# p2c-001.net
KiCad netlist of a schematic drawn in EAGLE
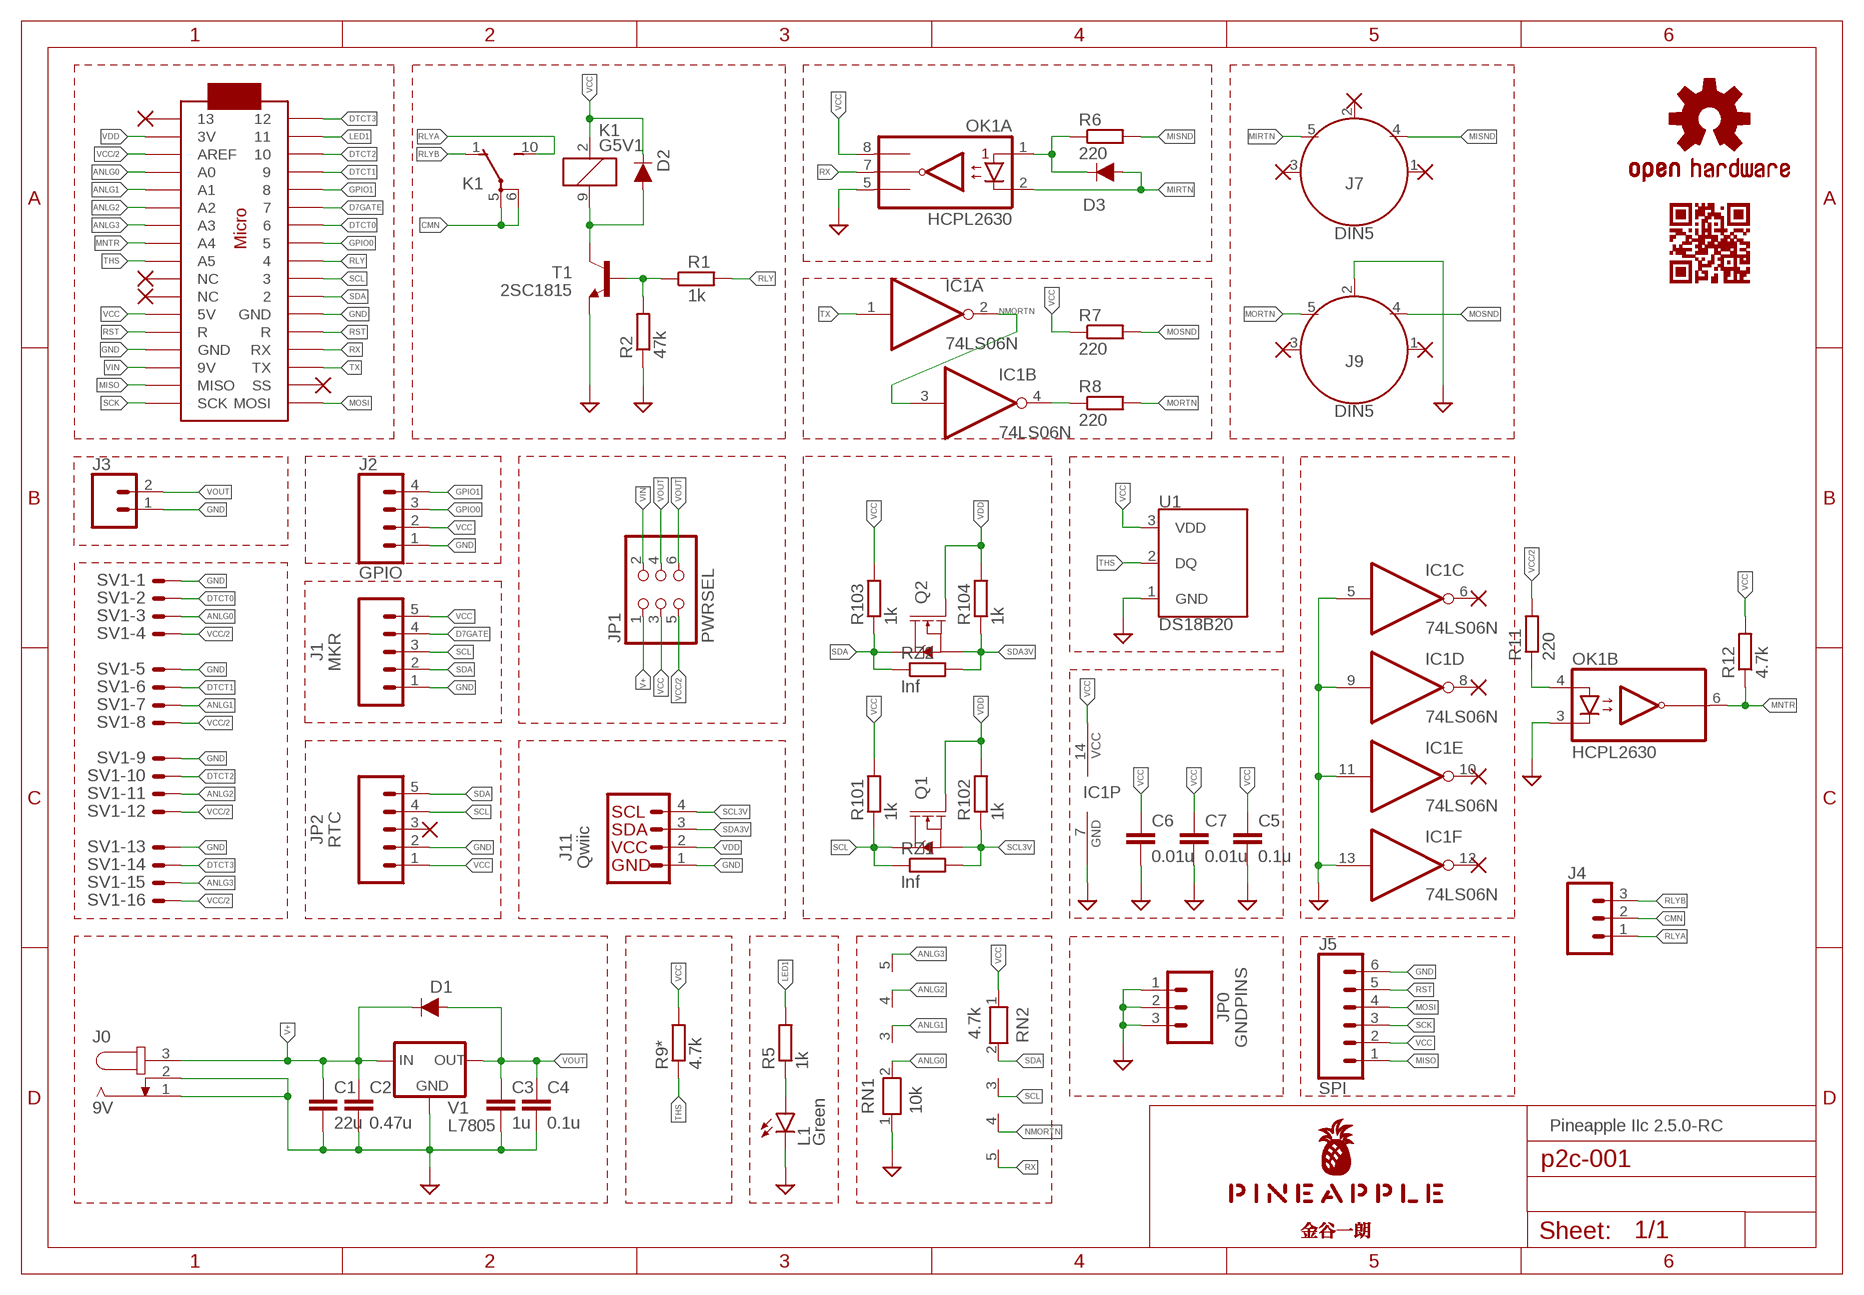
[diagram p0: schematic, sheet 1]

(export (version "E")
  (design (tool "Eeschema 10.0.6"))
  (components
    (comp (ref "C1")
      (value "22u")
      (footprint "eagle-import:C025-050X050")
      (libsource (lib "eagle-import") (part "C-EU025-050X050"))
    )
    (comp (ref "C2")
      (value "0.47u")
      (footprint "eagle-import:C050-024X044")
      (libsource (lib "eagle-import") (part "C-EU050-024X044"))
    )
    (comp (ref "C3")
      (value "1u")
      (footprint "eagle-import:C050-024X044")
      (libsource (lib "eagle-import") (part "C-EU050-024X044"))
    )
    (comp (ref "C4")
      (value "0.1u")
      (footprint "eagle-import:C025-024X044")
      (libsource (lib "eagle-import") (part "C-EU025-024X044"))
    )
    (comp (ref "C5")
      (value "0.1u")
      (footprint "eagle-import:C025-024X044")
      (libsource (lib "eagle-import") (part "C-EU025-024X044"))
    )
    (comp (ref "C6")
      (value "0.01u")
      (footprint "eagle-import:C025-024X044")
      (libsource (lib "eagle-import") (part "resistor_348_C-EU025-024X044"))
    )
    (comp (ref "C7")
      (value "0.01u")
      (footprint "eagle-import:C025-024X044")
      (libsource (lib "eagle-import") (part "resistor_348_C-EU025-024X044"))
    )
    (comp (ref "D1")
      (value "DIODE-1N4148")
      (footprint "eagle-import:DIODE-1N4148")
      (libsource (lib "eagle-import") (part "DIODE-1N4148"))
    )
    (comp (ref "D2")
      (value "DIODE-1N4148")
      (footprint "eagle-import:DIODE-1N4148")
      (libsource (lib "eagle-import") (part "DIODE-1N4148"))
    )
    (comp (ref "D3")
      (value "DIODE-1N4148")
      (footprint "eagle-import:DIODE-1N4148")
      (libsource (lib "eagle-import") (part "DIODE-1N4148"))
    )
    (comp (ref "IC1")
      (value "74LS06N")
      (footprint "eagle-import:DIL14")
      (libsource (lib "eagle-import") (part "7406NLS"))
    )
    (comp (ref "J0")
      (value "9V")
      (footprint "eagle-import:SPC4077")
      (libsource (lib "eagle-import") (part "JACK-PLUG0"))
    )
    (comp (ref "J1")
      (value "MKR")
      (footprint "eagle-import:JST-5-PTH")
      (libsource (lib "eagle-import") (part "CONN_05JST"))
    )
    (comp (ref "J2")
      (value "GPIO")
      (footprint "eagle-import:JST-4-PTH")
      (libsource (lib "eagle-import") (part "CONN_04JST-PTH"))
    )
    (comp (ref "J3")
      (value "CONN_02JST-PTH-2")
      (footprint "eagle-import:JST-2-PTH")
      (libsource (lib "eagle-import") (part "CONN_02JST-PTH-2"))
    )
    (comp (ref "J4")
      (value "CONN_03JST-PTH-NS")
      (footprint "eagle-import:JST-3-PTH-NS")
      (libsource (lib "eagle-import") (part "CONN_03JST-PTH-NS"))
    )
    (comp (ref "J5")
      (value "SPI")
      (footprint "eagle-import:1X06_1.27MM")
      (libsource (lib "eagle-import") (part "CONN_061.27MM"))
    )
    (comp (ref "J7")
      (value "DIN5")
      (footprint "eagle-import:DIN5-RA-PTH")
      (libsource (lib "eagle-import") (part "DIN5"))
    )
    (comp (ref "J9")
      (value "DIN5")
      (footprint "eagle-import:DIN5-RA-PTH")
      (libsource (lib "eagle-import") (part "DIN5"))
    )
    (comp (ref "J11")
      (value "Qwiic")
      (footprint "eagle-import:1X04_1MM_RA")
      (libsource (lib "eagle-import") (part "QWIIC_CONNECTORJS-1MM"))
    )
    (comp (ref "JP0")
      (value "GNDPINS")
      (footprint "eagle-import:1X03")
      (libsource (lib "eagle-import") (part "CONN_03"))
    )
    (comp (ref "JP1")
      (value "PWRSEL")
      (footprint "eagle-import:2X03")
      (libsource (lib "eagle-import") (part "PINHD-2X3"))
    )
    (comp (ref "JP2")
      (value "RTC")
      (footprint "eagle-import:1X05")
      (libsource (lib "eagle-import") (part "CONN_05"))
    )
    (comp (ref "K1")
      (value "G5V1")
      (footprint "eagle-import:G5V1")
      (fields (field (name "MPN") "G5V-1-DC24"))
      (libsource (lib "eagle-import") (part "G5V1"))
    )
    (comp (ref "L1")
      (value "Green")
      (footprint "eagle-import:LED3MM")
      (libsource (lib "eagle-import") (part "LED3MM"))
    )
    (comp (ref "LOGO1")
      (value "OSHW-LOGOS-COPPER")
      (footprint "eagle-import:OSHW-LOGO-S_COPPER")
      (libsource (lib "eagle-import") (part "OSHW-LOGOS-COPPER"))
    )
    (comp (ref "OK1")
      (value "HCPL2630")
      (footprint "eagle-import:DIL08")
      (fields (field (name "MF") "AGILENT TECHNOLOGIES") (field (name "MPN") "HCPL-2630-000E"))
      (libsource (lib "eagle-import") (part "HCPL2630"))
    )
    (comp (ref "Q1")
      (value "220mA/50V/3.5Ω")
      (footprint "eagle-import:SOT23-3")
      (libsource (lib "eagle-import") (part "MOSFET-NCH-BSS138"))
    )
    (comp (ref "Q2")
      (value "220mA/50V/3.5Ω")
      (footprint "eagle-import:SOT23-3")
      (libsource (lib "eagle-import") (part "MOSFET-NCH-BSS138"))
    )
    (comp (ref "R1")
      (value "1k")
      (footprint "eagle-import:0204_5")
      (libsource (lib "eagle-import") (part "R-EU_0204/5"))
    )
    (comp (ref "R2")
      (value "47k")
      (footprint "eagle-import:0204_5")
      (libsource (lib "eagle-import") (part "R-EU_0204/5"))
    )
    (comp (ref "R5")
      (value "1k")
      (footprint "eagle-import:0204_5")
      (libsource (lib "eagle-import") (part "R-EU_0204/5"))
    )
    (comp (ref "R6")
      (value "220")
      (footprint "eagle-import:0204_5")
      (libsource (lib "eagle-import") (part "R-EU_0204/5"))
    )
    (comp (ref "R7")
      (value "220")
      (footprint "eagle-import:0204_5")
      (libsource (lib "eagle-import") (part "R-EU_0204/5"))
    )
    (comp (ref "R8")
      (value "220")
      (footprint "eagle-import:0204_5")
      (libsource (lib "eagle-import") (part "R-EU_0204/5"))
    )
    (comp (ref "R9*")
      (value "4.7k")
      (footprint "eagle-import:0204_5")
      (libsource (lib "eagle-import") (part "R-EU_0204/5"))
    )
    (comp (ref "R11")
      (value "220")
      (footprint "eagle-import:0204_5")
      (libsource (lib "eagle-import") (part "R-EU_0204/5"))
    )
    (comp (ref "R12")
      (value "4.7k")
      (footprint "eagle-import:0204_5")
      (libsource (lib "eagle-import") (part "R-EU_0204/5"))
    )
    (comp (ref "R101")
      (value "1k")
      (footprint "eagle-import:R2012")
      (libsource (lib "eagle-import") (part "R-EU_R2012"))
    )
    (comp (ref "R102")
      (value "1k")
      (footprint "eagle-import:R2012")
      (libsource (lib "eagle-import") (part "R-EU_R2012"))
    )
    (comp (ref "R103")
      (value "1k")
      (footprint "eagle-import:R2012")
      (libsource (lib "eagle-import") (part "R-EU_R2012"))
    )
    (comp (ref "R104")
      (value "1k")
      (footprint "eagle-import:R2012")
      (libsource (lib "eagle-import") (part "R-EU_R2012"))
    )
    (comp (ref "RN1")
      (value "10k")
      (footprint "eagle-import:RN-5")
      (libsource (lib "eagle-import") (part "RN04"))
    )
    (comp (ref "RN2")
      (value "4.7k")
      (footprint "eagle-import:RN-5")
      (libsource (lib "eagle-import") (part "RN04"))
    )
    (comp (ref "RZ1")
      (value "Inf")
      (footprint "eagle-import:R2012")
      (libsource (lib "eagle-import") (part "R-EU_R2012"))
    )
    (comp (ref "RZ2")
      (value "Inf")
      (footprint "eagle-import:R2012")
      (libsource (lib "eagle-import") (part "R-EU_R2012"))
    )
    (comp (ref "SV1")
      (value "ML16LE")
      (footprint "eagle-import:ML16L")
      (libsource (lib "eagle-import") (part "ML16LE"))
    )
    (comp (ref "T1")
      (value "2SC1815")
      (footprint "eagle-import:TO92-ECB")
      (libsource (lib "eagle-import") (part "2SC1815"))
    )
    (comp (ref "U$1")
      (value "PINEAPPLE450_SILK")
      (footprint "eagle-import:PINEAPPLE450_SILK")
      (libsource (lib "eagle-import") (part "PINEAPPLE450_SILK"))
    )
    (comp (ref "U$2")
      (value "ARDUINOMICRO")
      (footprint "eagle-import:ARDUINOMICRO")
      (libsource (lib "eagle-import") (part "ARDUINOMICRO"))
    )
    (comp (ref "U$3")
      (value "KANAYA768_SILK")
      (footprint "eagle-import:KANAYA768_SILK")
      (libsource (lib "eagle-import") (part "KANAYA768_SILK"))
    )
    (comp (ref "U$4")
      (value "CARDQRCODE450_SILK")
      (footprint "eagle-import:CARDQRCODE450_SILK")
      (libsource (lib "eagle-import") (part "CARDQRCODE450_SILK"))
    )
    (comp (ref "U1")
      (value "DS18B20")
      (footprint "eagle-import:TO-92-AMMO")
      (libsource (lib "eagle-import") (part "DS18B20"))
    )
    (comp (ref "V1")
      (value "L7805")
      (footprint "eagle-import:78XXS")
      (libsource (lib "eagle-import") (part "78XXS"))
    )
  )
  (nets
    (net (code "1") (name "ANLG0") (class "Default")
      (node (ref "RN1") (pin "2") (pinfunction "2_2") (pintype "passive"))
      (node (ref "SV1") (pin "3") (pinfunction "S_3") (pintype "passive"))
      (node (ref "U$2") (pin "P$31") (pinfunction "A0_P$31") (pintype "bidirectional"))
    )
    (net (code "2") (name "ANLG1") (class "Default")
      (node (ref "RN1") (pin "3") (pinfunction "3_3") (pintype "passive"))
      (node (ref "SV1") (pin "7") (pinfunction "S_7") (pintype "passive"))
      (node (ref "U$2") (pin "P$30") (pinfunction "A1_P$30") (pintype "bidirectional"))
    )
    (net (code "3") (name "ANLG2") (class "Default")
      (node (ref "RN1") (pin "4") (pinfunction "4_4") (pintype "passive"))
      (node (ref "SV1") (pin "11") (pinfunction "S_11") (pintype "passive"))
      (node (ref "U$2") (pin "P$29") (pinfunction "A2_P$29") (pintype "bidirectional"))
    )
    (net (code "4") (name "ANLG3") (class "Default")
      (node (ref "RN1") (pin "5") (pinfunction "5_5") (pintype "passive"))
      (node (ref "SV1") (pin "15") (pinfunction "S_15") (pintype "passive"))
      (node (ref "U$2") (pin "P$28") (pinfunction "A3_P$28") (pintype "bidirectional"))
    )
    (net (code "5") (name "CMN") (class "Default")
      (node (ref "J4") (pin "2") (pinfunction "2_2") (pintype "passive"))
      (node (ref "K1") (pin "5") (pinfunction "P_5") (pintype "passive"))
      (node (ref "K1") (pin "6") (pinfunction "P_6") (pintype "passive"))
    )
    (net (code "6") (name "D7GATE") (class "Default")
      (node (ref "J1") (pin "4") (pinfunction "4_4") (pintype "passive"))
      (node (ref "U$2") (pin "P$6") (pinfunction "7_P$6") (pintype "bidirectional"))
    )
    (net (code "7") (name "DTCT0") (class "Default")
      (node (ref "SV1") (pin "2") (pinfunction "S_2") (pintype "passive"))
      (node (ref "U$2") (pin "P$7") (pinfunction "6_P$7") (pintype "bidirectional"))
    )
    (net (code "8") (name "DTCT1") (class "Default")
      (node (ref "SV1") (pin "6") (pinfunction "S_6") (pintype "passive"))
      (node (ref "U$2") (pin "P$4") (pinfunction "9_P$4") (pintype "bidirectional"))
    )
    (net (code "9") (name "DTCT2") (class "Default")
      (node (ref "SV1") (pin "10") (pinfunction "S_10") (pintype "passive"))
      (node (ref "U$2") (pin "P$3") (pinfunction "10_P$3") (pintype "bidirectional"))
    )
    (net (code "10") (name "DTCT3") (class "Default")
      (node (ref "SV1") (pin "14") (pinfunction "S_14") (pintype "passive"))
      (node (ref "U$2") (pin "P$1") (pinfunction "12_P$1") (pintype "bidirectional"))
    )
    (net (code "11") (name "GND") (class "Default")
      (node (ref "C1") (pin "2") (pinfunction "2_2") (pintype "passive"))
      (node (ref "C2") (pin "2") (pinfunction "2_2") (pintype "passive"))
      (node (ref "C3") (pin "2") (pinfunction "2_2") (pintype "passive"))
      (node (ref "C4") (pin "2") (pinfunction "2_2") (pintype "passive"))
      (node (ref "C5") (pin "2") (pinfunction "2_2") (pintype "passive"))
      (node (ref "C6") (pin "2") (pinfunction "2_2") (pintype "passive"))
      (node (ref "C7") (pin "2") (pinfunction "2_2") (pintype "passive"))
      (node (ref "IC1") (pin "11") (pinfunction "I_11") (pintype "input"))
      (node (ref "IC1") (pin "13") (pinfunction "I_13") (pintype "input"))
      (node (ref "IC1") (pin "5") (pinfunction "I_5") (pintype "input"))
      (node (ref "IC1") (pin "7") (pinfunction "GND_7") (pintype "power_in"))
      (node (ref "IC1") (pin "9") (pinfunction "I_9") (pintype "input"))
      (node (ref "J0") (pin "1") (pinfunction "1_1") (pintype "passive"))
      (node (ref "J0") (pin "2") (pinfunction "2_2") (pintype "passive"))
      (node (ref "J1") (pin "1") (pinfunction "1_1") (pintype "passive"))
      (node (ref "J11") (pin "1") (pinfunction "GND_1") (pintype "power_in"))
      (node (ref "J2") (pin "1") (pinfunction "1_1") (pintype "passive"))
      (node (ref "J3") (pin "1") (pinfunction "1_1") (pintype "passive"))
      (node (ref "J5") (pin "6") (pinfunction "6_6") (pintype "passive"))
      (node (ref "J9") (pin "2") (pinfunction "2_2") (pintype "bidirectional"))
      (node (ref "JP0") (pin "1") (pinfunction "1_1") (pintype "passive"))
      (node (ref "JP0") (pin "2") (pinfunction "2_2") (pintype "passive"))
      (node (ref "JP0") (pin "3") (pinfunction "3_3") (pintype "passive"))
      (node (ref "JP2") (pin "2") (pinfunction "2_2") (pintype "passive"))
      (node (ref "L1") (pin "K") (pinfunction "C_K") (pintype "passive"))
      (node (ref "OK1") (pin "3") (pinfunction "C2_3") (pintype "passive"))
      (node (ref "OK1") (pin "5") (pinfunction "GND_5") (pintype "passive"))
      (node (ref "R2") (pin "1") (pinfunction "1_1") (pintype "passive"))
      (node (ref "RN1") (pin "1") (pinfunction "1_1") (pintype "passive"))
      (node (ref "SV1") (pin "1") (pinfunction "S_1") (pintype "passive"))
      (node (ref "SV1") (pin "13") (pinfunction "S_13") (pintype "passive"))
      (node (ref "SV1") (pin "5") (pinfunction "S_5") (pintype "passive"))
      (node (ref "SV1") (pin "9") (pinfunction "S_9") (pintype "passive"))
      (node (ref "T1") (pin "E") (pinfunction "E_E") (pintype "passive"))
      (node (ref "U$2") (pin "P$12") (pinfunction "GND_P$12") (pintype "bidirectional"))
      (node (ref "U$2") (pin "P$21") (pinfunction "GND_P$21") (pintype "bidirectional"))
      (node (ref "U1") (pin "1") (pinfunction "GND_1") (pintype "power_in"))
      (node (ref "V1") (pin "GND") (pinfunction "GND_GND") (pintype "input"))
    )
    (net (code "12") (name "GPIO0") (class "Default")
      (node (ref "J2") (pin "3") (pinfunction "3_3") (pintype "passive"))
      (node (ref "U$2") (pin "P$8") (pinfunction "5_P$8") (pintype "bidirectional"))
    )
    (net (code "13") (name "GPIO1") (class "Default")
      (node (ref "J2") (pin "4") (pinfunction "4_4") (pintype "passive"))
      (node (ref "U$2") (pin "P$5") (pinfunction "8_P$5") (pintype "bidirectional"))
    )
    (net (code "14") (name "LED1") (class "Default")
      (node (ref "R5") (pin "2") (pinfunction "2_2") (pintype "passive"))
      (node (ref "U$2") (pin "P$2") (pinfunction "11_P$2") (pintype "bidirectional"))
    )
    (net (code "15") (name "MIRTN") (class "Default")
      (node (ref "D3") (pin "A") (pinfunction "A_A") (pintype "passive"))
      (node (ref "J7") (pin "5") (pinfunction "5_5") (pintype "bidirectional"))
      (node (ref "OK1") (pin "2") (pinfunction "C1_2") (pintype "passive"))
    )
    (net (code "16") (name "MISND") (class "Default")
      (node (ref "J7") (pin "4") (pinfunction "4_4") (pintype "bidirectional"))
      (node (ref "R6") (pin "2") (pinfunction "2_2") (pintype "passive"))
    )
    (net (code "17") (name "MISO") (class "Default")
      (node (ref "J5") (pin "1") (pinfunction "1_1") (pintype "passive"))
      (node (ref "U$2") (pin "P$19") (pinfunction "MISO_P$19") (pintype "bidirectional"))
    )
    (net (code "18") (name "MNTR") (class "Default")
      (node (ref "OK1") (pin "6") (pinfunction "VO2_6") (pintype "passive"))
      (node (ref "R12") (pin "1") (pinfunction "1_1") (pintype "passive"))
      (node (ref "U$2") (pin "P$27") (pinfunction "A4_P$27") (pintype "bidirectional"))
    )
    (net (code "19") (name "MORTN") (class "Default")
      (node (ref "J9") (pin "5") (pinfunction "5_5") (pintype "bidirectional"))
      (node (ref "R8") (pin "2") (pinfunction "2_2") (pintype "passive"))
    )
    (net (code "20") (name "MOSI") (class "Default")
      (node (ref "J5") (pin "4") (pinfunction "4_4") (pintype "passive"))
      (node (ref "U$2") (pin "P$17") (pinfunction "MOSI_P$17") (pintype "bidirectional"))
    )
    (net (code "21") (name "MOSND") (class "Default")
      (node (ref "J9") (pin "4") (pinfunction "4_4") (pintype "bidirectional"))
      (node (ref "R7") (pin "2") (pinfunction "2_2") (pintype "passive"))
    )
    (net (code "22") (name "NMORTN") (class "Default")
      (node (ref "IC1") (pin "2") (pinfunction "O_2") (pintype "open_collector"))
      (node (ref "IC1") (pin "3") (pinfunction "I_3") (pintype "input"))
      (node (ref "RN2") (pin "4") (pinfunction "4_4") (pintype "passive"))
    )
    (net (code "23") (name "Net-(IC1B-O)") (class "Default")
      (node (ref "IC1") (pin "4") (pinfunction "O_4") (pintype "open_collector"))
      (node (ref "R8") (pin "1") (pinfunction "1_1") (pintype "passive"))
    )
    (net (code "24") (name "Net-(K1A-2)") (class "Default")
      (node (ref "D2") (pin "A") (pinfunction "A_A") (pintype "passive"))
      (node (ref "K1") (pin "9") (pinfunction "2_9") (pintype "passive"))
      (node (ref "T1") (pin "C") (pinfunction "C_C") (pintype "passive"))
    )
    (net (code "25") (name "Net-(L1-PadA)") (class "Default")
      (node (ref "L1") (pin "A") (pinfunction "A_A") (pintype "passive"))
      (node (ref "R5") (pin "1") (pinfunction "1_1") (pintype "passive"))
    )
    (net (code "26") (name "Net-(OK1A-A1)") (class "Default")
      (node (ref "D3") (pin "C") (pinfunction "C_C") (pintype "passive"))
      (node (ref "OK1") (pin "1") (pinfunction "A1_1") (pintype "passive"))
      (node (ref "R6") (pin "1") (pinfunction "1_1") (pintype "passive"))
    )
    (net (code "27") (name "Net-(OK1B-A2)") (class "Default")
      (node (ref "OK1") (pin "4") (pinfunction "A2_4") (pintype "passive"))
      (node (ref "R11") (pin "1") (pinfunction "1_1") (pintype "passive"))
    )
    (net (code "28") (name "Net-(R1-Pad1)") (class "Default")
      (node (ref "R1") (pin "1") (pinfunction "1_1") (pintype "passive"))
      (node (ref "R2") (pin "2") (pinfunction "2_2") (pintype "passive"))
      (node (ref "T1") (pin "B") (pinfunction "B_B") (pintype "passive"))
    )
    (net (code "29") (name "RLY") (class "Default")
      (node (ref "R1") (pin "2") (pinfunction "2_2") (pintype "passive"))
      (node (ref "U$2") (pin "P$9") (pinfunction "4_P$9") (pintype "bidirectional"))
    )
    (net (code "30") (name "RLYA") (class "Default")
      (node (ref "J4") (pin "1") (pinfunction "1_1") (pintype "passive"))
      (node (ref "K1") (pin "10") (pinfunction "S_10") (pintype "passive"))
    )
    (net (code "31") (name "RLYB") (class "Default")
      (node (ref "J4") (pin "3") (pinfunction "3_3") (pintype "passive"))
      (node (ref "K1") (pin "1") (pinfunction "O_1") (pintype "passive"))
    )
    (net (code "32") (name "RST") (class "Default")
      (node (ref "J5") (pin "5") (pinfunction "5_5") (pintype "passive"))
      (node (ref "U$2") (pin "P$13") (pinfunction "R_P$13") (pintype "bidirectional"))
      (node (ref "U$2") (pin "P$22") (pinfunction "R_P$22") (pintype "bidirectional"))
    )
    (net (code "33") (name "RX") (class "Default")
      (node (ref "OK1") (pin "7") (pinfunction "VO1_7") (pintype "passive"))
      (node (ref "RN2") (pin "5") (pinfunction "5_5") (pintype "passive"))
      (node (ref "U$2") (pin "P$14") (pinfunction "RX_P$14") (pintype "bidirectional"))
    )
    (net (code "34") (name "SCK") (class "Default")
      (node (ref "J5") (pin "3") (pinfunction "3_3") (pintype "passive"))
      (node (ref "U$2") (pin "P$18") (pinfunction "SCK_P$18") (pintype "bidirectional"))
    )
    (net (code "35") (name "SCL") (class "Default")
      (node (ref "J1") (pin "3") (pinfunction "3_3") (pintype "passive"))
      (node (ref "JP2") (pin "4") (pinfunction "4_4") (pintype "passive"))
      (node (ref "Q1") (pin "3") (pinfunction "D_3") (pintype "bidirectional"))
      (node (ref "R101") (pin "1") (pinfunction "1_1") (pintype "passive"))
      (node (ref "RN2") (pin "3") (pinfunction "3_3") (pintype "passive"))
      (node (ref "RZ1") (pin "1") (pinfunction "1_1") (pintype "passive"))
      (node (ref "U$2") (pin "P$10") (pinfunction "3_P$10") (pintype "bidirectional"))
    )
    (net (code "36") (name "SCL3V") (class "Default")
      (node (ref "J11") (pin "4") (pinfunction "SCL_4") (pintype "passive"))
      (node (ref "Q1") (pin "2") (pinfunction "S_2") (pintype "bidirectional"))
      (node (ref "R102") (pin "1") (pinfunction "1_1") (pintype "passive"))
      (node (ref "RZ1") (pin "2") (pinfunction "2_2") (pintype "passive"))
    )
    (net (code "37") (name "SDA") (class "Default")
      (node (ref "J1") (pin "2") (pinfunction "2_2") (pintype "passive"))
      (node (ref "JP2") (pin "5") (pinfunction "5_5") (pintype "passive"))
      (node (ref "Q2") (pin "3") (pinfunction "D_3") (pintype "bidirectional"))
      (node (ref "R103") (pin "1") (pinfunction "1_1") (pintype "passive"))
      (node (ref "RN2") (pin "2") (pinfunction "2_2") (pintype "passive"))
      (node (ref "RZ2") (pin "1") (pinfunction "1_1") (pintype "passive"))
      (node (ref "U$2") (pin "P$11") (pinfunction "2_P$11") (pintype "bidirectional"))
    )
    (net (code "38") (name "SDA3V") (class "Default")
      (node (ref "J11") (pin "3") (pinfunction "SDA_3") (pintype "passive"))
      (node (ref "Q2") (pin "2") (pinfunction "S_2") (pintype "bidirectional"))
      (node (ref "R104") (pin "1") (pinfunction "1_1") (pintype "passive"))
      (node (ref "RZ2") (pin "2") (pinfunction "2_2") (pintype "passive"))
    )
    (net (code "39") (name "THS") (class "Default")
      (node (ref "R9*") (pin "1") (pinfunction "1_1") (pintype "passive"))
      (node (ref "U$2") (pin "P$26") (pinfunction "A5_P$26") (pintype "bidirectional"))
      (node (ref "U1") (pin "2") (pinfunction "DQ_2") (pintype "bidirectional"))
    )
    (net (code "40") (name "TX") (class "Default")
      (node (ref "IC1") (pin "1") (pinfunction "I_1") (pintype "input"))
      (node (ref "U$2") (pin "P$15") (pinfunction "TX_P$15") (pintype "bidirectional"))
    )
    (net (code "41") (name "V+") (class "Default")
      (node (ref "C1") (pin "1") (pinfunction "1_1") (pintype "passive"))
      (node (ref "C2") (pin "1") (pinfunction "1_1") (pintype "passive"))
      (node (ref "D1") (pin "C") (pinfunction "C_C") (pintype "passive"))
      (node (ref "J0") (pin "3") (pinfunction "3_3") (pintype "passive"))
      (node (ref "JP1") (pin "1") (pinfunction "1_1") (pintype "passive"))
      (node (ref "V1") (pin "IN") (pinfunction "IN_IN") (pintype "input"))
    )
    (net (code "42") (name "VCC") (class "Default")
      (node (ref "C5") (pin "1") (pinfunction "1_1") (pintype "passive"))
      (node (ref "C6") (pin "1") (pinfunction "1_1") (pintype "passive"))
      (node (ref "C7") (pin "1") (pinfunction "1_1") (pintype "passive"))
      (node (ref "D2") (pin "C") (pinfunction "C_C") (pintype "passive"))
      (node (ref "IC1") (pin "14") (pinfunction "VCC_14") (pintype "power_in"))
      (node (ref "J1") (pin "5") (pinfunction "5_5") (pintype "passive"))
      (node (ref "J2") (pin "2") (pinfunction "2_2") (pintype "passive"))
      (node (ref "J5") (pin "2") (pinfunction "2_2") (pintype "passive"))
      (node (ref "JP1") (pin "3") (pinfunction "3_3") (pintype "passive"))
      (node (ref "JP2") (pin "1") (pinfunction "1_1") (pintype "passive"))
      (node (ref "K1") (pin "2") (pinfunction "1_2") (pintype "passive"))
      (node (ref "OK1") (pin "8") (pinfunction "VCC_8") (pintype "passive"))
      (node (ref "R101") (pin "2") (pinfunction "2_2") (pintype "passive"))
      (node (ref "R103") (pin "2") (pinfunction "2_2") (pintype "passive"))
      (node (ref "R12") (pin "2") (pinfunction "2_2") (pintype "passive"))
      (node (ref "R7") (pin "1") (pinfunction "1_1") (pintype "passive"))
      (node (ref "R9*") (pin "2") (pinfunction "2_2") (pintype "passive"))
      (node (ref "RN2") (pin "1") (pinfunction "1_1") (pintype "passive"))
      (node (ref "U$2") (pin "P$23") (pinfunction "5V_P$23") (pintype "bidirectional"))
      (node (ref "U1") (pin "3") (pinfunction "VDD_3") (pintype "power_in"))
    )
    (net (code "43") (name "VCC{slash}2") (class "Default")
      (node (ref "JP1") (pin "5") (pinfunction "5_5") (pintype "passive"))
      (node (ref "R11") (pin "2") (pinfunction "2_2") (pintype "passive"))
      (node (ref "SV1") (pin "12") (pinfunction "S_12") (pintype "passive"))
      (node (ref "SV1") (pin "16") (pinfunction "S_16") (pintype "passive"))
      (node (ref "SV1") (pin "4") (pinfunction "S_4") (pintype "passive"))
      (node (ref "SV1") (pin "8") (pinfunction "S_8") (pintype "passive"))
      (node (ref "U$2") (pin "P$32") (pinfunction "AREF_P$32") (pintype "bidirectional"))
    )
    (net (code "44") (name "VDD") (class "Default")
      (node (ref "J11") (pin "2") (pinfunction "VCC_2") (pintype "power_in"))
      (node (ref "Q1") (pin "1") (pinfunction "G_1") (pintype "bidirectional"))
      (node (ref "Q2") (pin "1") (pinfunction "G_1") (pintype "bidirectional"))
      (node (ref "R102") (pin "2") (pinfunction "2_2") (pintype "passive"))
      (node (ref "R104") (pin "2") (pinfunction "2_2") (pintype "passive"))
      (node (ref "U$2") (pin "P$33") (pinfunction "3V_P$33") (pintype "bidirectional"))
    )
    (net (code "45") (name "VIN") (class "Default")
      (node (ref "JP1") (pin "2") (pinfunction "2_2") (pintype "passive"))
      (node (ref "U$2") (pin "P$20") (pinfunction "9V_P$20") (pintype "bidirectional"))
    )
    (net (code "46") (name "VOUT") (class "Default")
      (node (ref "C3") (pin "1") (pinfunction "1_1") (pintype "passive"))
      (node (ref "C4") (pin "1") (pinfunction "1_1") (pintype "passive"))
      (node (ref "D1") (pin "A") (pinfunction "A_A") (pintype "passive"))
      (node (ref "J3") (pin "2") (pinfunction "2_2") (pintype "passive"))
      (node (ref "JP1") (pin "4") (pinfunction "4_4") (pintype "passive"))
      (node (ref "JP1") (pin "6") (pinfunction "6_6") (pintype "passive"))
      (node (ref "V1") (pin "OUT") (pinfunction "OUT_OUT") (pintype "passive"))
    )
    (net (code "47") (name "unconnected-(IC1C-O-Pad6)") (class "Default")
      (node (ref "IC1") (pin "6") (pinfunction "O_6") (pintype "open_collector"))
    )
    (net (code "48") (name "unconnected-(IC1D-O-Pad8)") (class "Default")
      (node (ref "IC1") (pin "8") (pinfunction "O_8") (pintype "open_collector"))
    )
    (net (code "49") (name "unconnected-(IC1E-O-Pad10)") (class "Default")
      (node (ref "IC1") (pin "10") (pinfunction "O_10") (pintype "open_collector"))
    )
    (net (code "50") (name "unconnected-(IC1F-O-Pad12)") (class "Default")
      (node (ref "IC1") (pin "12") (pinfunction "O_12") (pintype "open_collector"))
    )
    (net (code "51") (name "unconnected-(J7-Pad1)") (class "Default")
      (node (ref "J7") (pin "1") (pinfunction "1_1") (pintype "bidirectional"))
    )
    (net (code "52") (name "unconnected-(J7-Pad2)") (class "Default")
      (node (ref "J7") (pin "2") (pinfunction "2_2") (pintype "bidirectional"))
    )
    (net (code "53") (name "unconnected-(J7-Pad3)") (class "Default")
      (node (ref "J7") (pin "3") (pinfunction "3_3") (pintype "bidirectional"))
    )
    (net (code "54") (name "unconnected-(J9-Pad1)") (class "Default")
      (node (ref "J9") (pin "1") (pinfunction "1_1") (pintype "bidirectional"))
    )
    (net (code "55") (name "unconnected-(J9-Pad3)") (class "Default")
      (node (ref "J9") (pin "3") (pinfunction "3_3") (pintype "bidirectional"))
    )
    (net (code "56") (name "unconnected-(JP2-Pad3)") (class "Default")
      (node (ref "JP2") (pin "3") (pinfunction "3_3") (pintype "passive"))
    )
    (net (code "57") (name "unconnected-(U$2-13-PadP$34)") (class "Default")
      (node (ref "U$2") (pin "P$34") (pinfunction "13_P$34") (pintype "bidirectional"))
    )
    (net (code "58") (name "unconnected-(U$2-NC-PadP$24)") (class "Default")
      (node (ref "U$2") (pin "P$24") (pinfunction "NC_P$24") (pintype "bidirectional"))
    )
    (net (code "59") (name "unconnected-(U$2-NC-PadP$25)") (class "Default")
      (node (ref "U$2") (pin "P$25") (pinfunction "NC_P$25") (pintype "bidirectional"))
    )
    (net (code "60") (name "unconnected-(U$2-SS-PadP$16)") (class "Default")
      (node (ref "U$2") (pin "P$16") (pinfunction "SS_P$16") (pintype "bidirectional"))
    )
  )
)
